# imx6_boot.net
KiCad netlist of a schematic drawn in Altium Designer
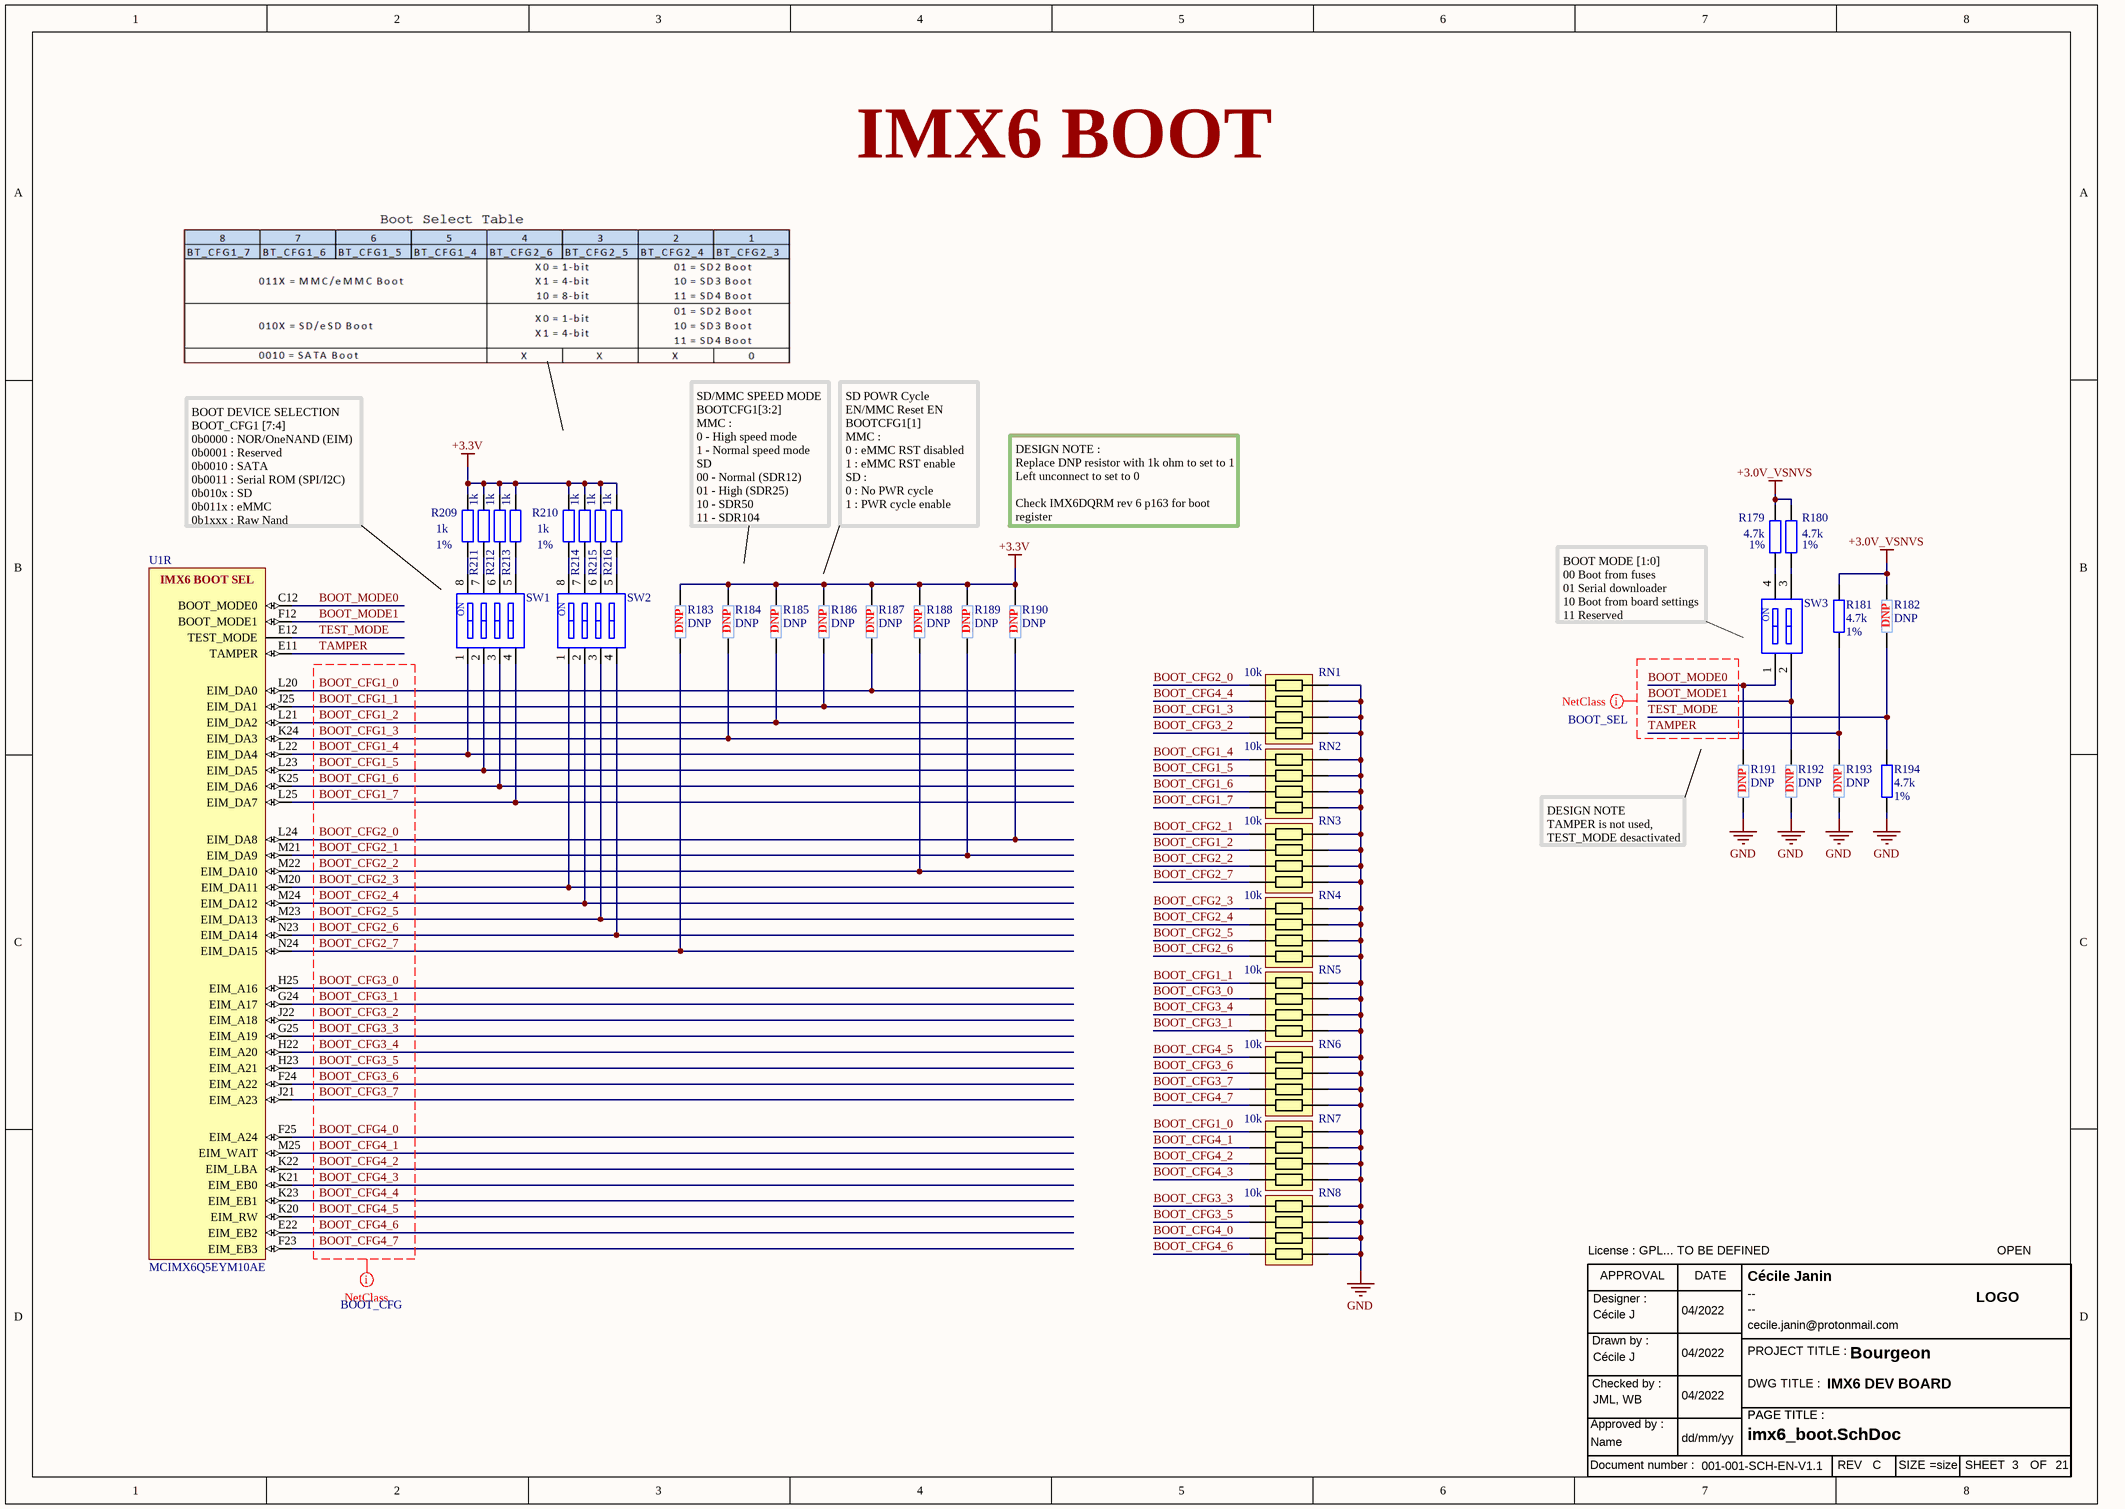
[diagram p0: imx6_boot.SchDoc]

(export (version "E")
  (design (tool "Eeschema 10.0.6"))
  (components
    (comp (ref "R179")
      (value "4.7k")
      (footprint "Res 0402/1005")
      (description "res 4.7k 1% 0402")
      (fields (field (name "POURCENTAGE") "1%"))
      (libsource (lib "First Board IMX6") (part "res 4.7k 1%"))
    )
    (comp (ref "R180")
      (value "4.7k")
      (footprint "Res 0402/1005")
      (description "res 4.7k 1% 0402")
      (fields (field (name "POURCENTAGE") "1%"))
      (libsource (lib "First Board IMX6") (part "res 4.7k 1%"))
    )
    (comp (ref "R181")
      (value "4.7k")
      (footprint "Res 0402/1005")
      (description "res 4.7k 1% 0402")
      (fields (field (name "POURCENTAGE") "1%"))
      (libsource (lib "First Board IMX6") (part "res 4.7k 1%"))
    )
    (comp (ref "R182")
      (value "DNP")
      (footprint "Res 0402/1005")
      (description "res DNP 0403")
      (libsource (lib "First Board IMX6") (part "res DNP 0402"))
    )
    (comp (ref "R183")
      (value "DNP")
      (footprint "Res 0402/1005")
      (description "res DNP 0403")
      (libsource (lib "First Board IMX6") (part "res DNP 0402"))
    )
    (comp (ref "R184")
      (value "DNP")
      (footprint "Res 0402/1005")
      (description "res DNP 0403")
      (libsource (lib "First Board IMX6") (part "res DNP 0402"))
    )
    (comp (ref "R185")
      (value "DNP")
      (footprint "Res 0402/1005")
      (description "res DNP 0403")
      (libsource (lib "First Board IMX6") (part "res DNP 0402"))
    )
    (comp (ref "R186")
      (value "DNP")
      (footprint "Res 0402/1005")
      (description "res DNP 0403")
      (libsource (lib "First Board IMX6") (part "res DNP 0402"))
    )
    (comp (ref "R187")
      (value "DNP")
      (footprint "Res 0402/1005")
      (description "res DNP 0403")
      (libsource (lib "First Board IMX6") (part "res DNP 0402"))
    )
    (comp (ref "R188")
      (value "DNP")
      (footprint "Res 0402/1005")
      (description "res DNP 0403")
      (libsource (lib "First Board IMX6") (part "res DNP 0402"))
    )
    (comp (ref "R189")
      (value "DNP")
      (footprint "Res 0402/1005")
      (description "res DNP 0403")
      (libsource (lib "First Board IMX6") (part "res DNP 0402"))
    )
    (comp (ref "R190")
      (value "DNP")
      (footprint "Res 0402/1005")
      (description "res DNP 0403")
      (libsource (lib "First Board IMX6") (part "res DNP 0402"))
    )
    (comp (ref "R191")
      (value "DNP")
      (footprint "Res 0402/1005")
      (description "res DNP 0403")
      (libsource (lib "First Board IMX6") (part "res DNP 0402"))
    )
    (comp (ref "R192")
      (value "DNP")
      (footprint "Res 0402/1005")
      (description "res DNP 0403")
      (libsource (lib "First Board IMX6") (part "res DNP 0402"))
    )
    (comp (ref "R193")
      (value "DNP")
      (footprint "Res 0402/1005")
      (description "res DNP 0403")
      (libsource (lib "First Board IMX6") (part "res DNP 0402"))
    )
    (comp (ref "R194")
      (value "4.7k")
      (footprint "Res 0402/1005")
      (description "res 4.7k 1% 0402")
      (fields (field (name "POURCENTAGE") "1%"))
      (libsource (lib "First Board IMX6") (part "res 4.7k 1%"))
    )
    (comp (ref "R209")
      (value "1k")
      (footprint "Res 0402/1005")
      (description "res 1k 1% 0402")
      (fields (field (name "POURCENTAGE") "1%"))
      (libsource (lib "First Board IMX6") (part "res 1k 1%"))
    )
    (comp (ref "R210")
      (value "1k")
      (footprint "Res 0402/1005")
      (description "res 1k 1% 0402")
      (fields (field (name "POURCENTAGE") "1%"))
      (libsource (lib "First Board IMX6") (part "res 1k 1%"))
    )
    (comp (ref "R211")
      (value "1k")
      (footprint "Res 0402/1005")
      (description "res 1k 1% 0402")
      (libsource (lib "First Board IMX6") (part "res 1k 1%"))
    )
    (comp (ref "R212")
      (value "1k")
      (footprint "Res 0402/1005")
      (description "res 1k 1% 0402")
      (libsource (lib "First Board IMX6") (part "res 1k 1%"))
    )
    (comp (ref "R213")
      (value "1k")
      (footprint "Res 0402/1005")
      (description "res 1k 1% 0402")
      (libsource (lib "First Board IMX6") (part "res 1k 1%"))
    )
    (comp (ref "R214")
      (value "1k")
      (footprint "Res 0402/1005")
      (description "res 1k 1% 0402")
      (libsource (lib "First Board IMX6") (part "res 1k 1%"))
    )
    (comp (ref "R215")
      (value "1k")
      (footprint "Res 0402/1005")
      (description "res 1k 1% 0402")
      (libsource (lib "First Board IMX6") (part "res 1k 1%"))
    )
    (comp (ref "R216")
      (value "1k")
      (footprint "Res 0402/1005")
      (description "res 1k 1% 0402")
      (libsource (lib "First Board IMX6") (part "res 1k 1%"))
    )
    (comp (ref "RN1")
      (value "10k")
      (footprint "res net x4  EXB-28V103JX")
      (description "resistor network 10k 5% x4 EXB-28V103JX")
      (libsource (lib "First Board IMX6") (part "res 10k net x4"))
    )
    (comp (ref "RN2")
      (value "10k")
      (footprint "res net x4  EXB-28V103JX")
      (description "resistor network 10k 5% x4 EXB-28V103JX")
      (libsource (lib "") (part "res 10k net x4_1"))
    )
    (comp (ref "RN3")
      (value "10k")
      (footprint "res net x4  EXB-28V103JX")
      (description "resistor network 10k 5% x4 EXB-28V103JX")
      (libsource (lib "First Board IMX6") (part "res 10k net x4"))
    )
    (comp (ref "RN4")
      (value "10k")
      (footprint "res net x4  EXB-28V103JX")
      (description "resistor network 10k 5% x4 EXB-28V103JX")
      (libsource (lib "") (part "res 10k net x4_1"))
    )
    (comp (ref "RN5")
      (value "10k")
      (footprint "res net x4  EXB-28V103JX")
      (description "resistor network 10k 5% x4 EXB-28V103JX")
      (libsource (lib "First Board IMX6") (part "res 10k net x4"))
    )
    (comp (ref "RN6")
      (value "10k")
      (footprint "res net x4  EXB-28V103JX")
      (description "resistor network 10k 5% x4 EXB-28V103JX")
      (libsource (lib "First Board IMX6") (part "res 10k net x4"))
    )
    (comp (ref "RN7")
      (value "10k")
      (footprint "res net x4  EXB-28V103JX")
      (description "resistor network 10k 5% x4 EXB-28V103JX")
      (libsource (lib "First Board IMX6") (part "res 10k net x4"))
    )
    (comp (ref "RN8")
      (value "10k")
      (footprint "res net x4  EXB-28V103JX")
      (description "resistor network 10k 5% x4 EXB-28V103JX")
      (libsource (lib "First Board IMX6") (part "res 10k net x4"))
    )
    (comp (ref "SW1")
      (value "416131160804")
      (footprint "DIP SWITCH x4 1.27mm")
      (libsource (lib "First Board IMX6") (part "DIP switch x4"))
    )
    (comp (ref "SW2")
      (value "416131160804")
      (footprint "DIP SWITCH x4 1.27mm")
      (libsource (lib "First Board IMX6") (part "DIP switch x4"))
    )
    (comp (ref "SW3")
      (value "416131160802")
      (footprint "DIP switch x2 1.27mm")
      (libsource (lib "First Board IMX6") (part "DIP switch x2"))
    )
    (comp (ref "TB20")
      (value "Title bloc ANSI modified")
      (libsource (lib "First Board IMX6") (part "Title bloc ANSI"))
    )
    (comp (ref "U1")
      (value "MCIMX6Q5EYM10AE")
      (footprint "FRES-2197-01")
      (fields
        (field (name "PARTNUMBER") "MCIMX6Q5EYM10ACR")
        (field (name "MANUFACTURER") "Freescale Semiconductor")
      )
      (libsource (lib "First Board IMX6") (part "IMX6Q5EYM10AE"))
    )
  )
  (nets
    (net (code "1") (name "+3.0V_VSNVS") (class "Default")
      (node (ref "R179") (pin "2") (pintype "passive"))
      (node (ref "R180") (pin "2") (pintype "passive"))
      (node (ref "R181") (pin "2") (pintype "passive"))
      (node (ref "R182") (pin "2") (pintype "passive"))
    )
    (net (code "2") (name "+3.3V") (class "Default")
      (node (ref "R183") (pin "2") (pintype "passive"))
      (node (ref "R184") (pin "2") (pintype "passive"))
      (node (ref "R185") (pin "2") (pintype "passive"))
      (node (ref "R186") (pin "2") (pintype "passive"))
      (node (ref "R187") (pin "2") (pintype "passive"))
      (node (ref "R188") (pin "2") (pintype "passive"))
      (node (ref "R189") (pin "2") (pintype "passive"))
      (node (ref "R190") (pin "2") (pintype "passive"))
      (node (ref "R209") (pin "2") (pintype "passive"))
      (node (ref "R210") (pin "2") (pintype "passive"))
      (node (ref "R211") (pin "2") (pintype "passive"))
      (node (ref "R212") (pin "2") (pintype "passive"))
      (node (ref "R213") (pin "2") (pintype "passive"))
      (node (ref "R214") (pin "2") (pintype "passive"))
      (node (ref "R215") (pin "2") (pintype "passive"))
      (node (ref "R216") (pin "2") (pintype "passive"))
    )
    (net (code "3") (name "/BOOT_CFG1_0") (class "Default")
      (node (ref "R187") (pin "1") (pintype "passive"))
      (node (ref "RN7") (pin "1") (pinfunction "1_1") (pintype "passive"))
      (node (ref "U1") (pin "L20") (pinfunction "EIM_DA0_L20") (pintype "bidirectional"))
    )
    (net (code "4") (name "/BOOT_CFG1_1") (class "Default")
      (node (ref "R186") (pin "1") (pintype "passive"))
      (node (ref "RN5") (pin "1") (pinfunction "1_1") (pintype "passive"))
      (node (ref "U1") (pin "J25") (pinfunction "EIM_DA1_J25") (pintype "bidirectional"))
    )
    (net (code "5") (name "/BOOT_CFG1_2") (class "Default")
      (node (ref "R185") (pin "1") (pintype "passive"))
      (node (ref "RN3") (pin "2") (pinfunction "2_2") (pintype "passive"))
      (node (ref "U1") (pin "L21") (pinfunction "EIM_DA2_L21") (pintype "bidirectional"))
    )
    (net (code "6") (name "/BOOT_CFG1_3") (class "Default")
      (node (ref "R184") (pin "1") (pintype "passive"))
      (node (ref "RN1") (pin "3") (pinfunction "3_3") (pintype "passive"))
      (node (ref "U1") (pin "K24") (pinfunction "EIM_DA3_K24") (pintype "bidirectional"))
    )
    (net (code "7") (name "/BOOT_CFG1_4") (class "Default")
      (node (ref "RN2") (pin "8") (pinfunction "8_8") (pintype "passive"))
      (node (ref "SW1") (pin "1") (pinfunction "1_1") (pintype "passive"))
      (node (ref "U1") (pin "L22") (pinfunction "EIM_DA4_L22") (pintype "bidirectional"))
    )
    (net (code "8") (name "/BOOT_CFG1_5") (class "Default")
      (node (ref "RN2") (pin "7") (pinfunction "7_7") (pintype "passive"))
      (node (ref "SW1") (pin "2") (pinfunction "2_2") (pintype "passive"))
      (node (ref "U1") (pin "L23") (pinfunction "EIM_DA5_L23") (pintype "bidirectional"))
    )
    (net (code "9") (name "/BOOT_CFG1_6") (class "Default")
      (node (ref "RN2") (pin "6") (pinfunction "1_6") (pintype "passive"))
      (node (ref "SW1") (pin "3") (pinfunction "3_3") (pintype "passive"))
      (node (ref "U1") (pin "K25") (pinfunction "EIM_DA6_K25") (pintype "bidirectional"))
    )
    (net (code "10") (name "/BOOT_CFG1_7") (class "Default")
      (node (ref "RN2") (pin "5") (pinfunction "5_5") (pintype "passive"))
      (node (ref "SW1") (pin "4") (pinfunction "4_4") (pintype "passive"))
      (node (ref "U1") (pin "L25") (pinfunction "EIM_DA7_L25") (pintype "bidirectional"))
    )
    (net (code "11") (name "/BOOT_CFG2_0") (class "Default")
      (node (ref "R190") (pin "1") (pintype "passive"))
      (node (ref "RN1") (pin "1") (pinfunction "1_1") (pintype "passive"))
      (node (ref "U1") (pin "L24") (pinfunction "EIM_DA8_L24") (pintype "bidirectional"))
    )
    (net (code "12") (name "/BOOT_CFG2_1") (class "Default")
      (node (ref "R189") (pin "1") (pintype "passive"))
      (node (ref "RN3") (pin "1") (pinfunction "1_1") (pintype "passive"))
      (node (ref "U1") (pin "M21") (pinfunction "EIM_DA9_M21") (pintype "bidirectional"))
    )
    (net (code "13") (name "/BOOT_CFG2_2") (class "Default")
      (node (ref "R188") (pin "1") (pintype "passive"))
      (node (ref "RN3") (pin "3") (pinfunction "3_3") (pintype "passive"))
      (node (ref "U1") (pin "M22") (pinfunction "EIM_DA10_M22") (pintype "bidirectional"))
    )
    (net (code "14") (name "/BOOT_CFG2_3") (class "Default")
      (node (ref "RN4") (pin "8") (pinfunction "8_8") (pintype "passive"))
      (node (ref "SW2") (pin "1") (pinfunction "1_1") (pintype "passive"))
      (node (ref "U1") (pin "M20") (pinfunction "EIM_DA11_M20") (pintype "bidirectional"))
    )
    (net (code "15") (name "/BOOT_CFG2_4") (class "Default")
      (node (ref "RN4") (pin "7") (pinfunction "7_7") (pintype "passive"))
      (node (ref "SW2") (pin "2") (pinfunction "2_2") (pintype "passive"))
      (node (ref "U1") (pin "M24") (pinfunction "EIM_DA12_M24") (pintype "bidirectional"))
    )
    (net (code "16") (name "/BOOT_CFG2_5") (class "Default")
      (node (ref "RN4") (pin "6") (pinfunction "1_6") (pintype "passive"))
      (node (ref "SW2") (pin "3") (pinfunction "3_3") (pintype "passive"))
      (node (ref "U1") (pin "M23") (pinfunction "EIM_DA13_M23") (pintype "bidirectional"))
    )
    (net (code "17") (name "/BOOT_CFG2_6") (class "Default")
      (node (ref "RN4") (pin "5") (pinfunction "5_5") (pintype "passive"))
      (node (ref "SW2") (pin "4") (pinfunction "4_4") (pintype "passive"))
      (node (ref "U1") (pin "N23") (pinfunction "EIM_DA14_N23") (pintype "bidirectional"))
    )
    (net (code "18") (name "/BOOT_CFG2_7") (class "Default")
      (node (ref "R183") (pin "1") (pintype "passive"))
      (node (ref "RN3") (pin "4") (pinfunction "4_4") (pintype "passive"))
      (node (ref "U1") (pin "N24") (pinfunction "EIM_DA15_N24") (pintype "bidirectional"))
    )
    (net (code "19") (name "/BOOT_CFG3_0") (class "Default")
      (node (ref "RN5") (pin "2") (pinfunction "2_2") (pintype "passive"))
      (node (ref "U1") (pin "H25") (pinfunction "EIM_A16_H25") (pintype "bidirectional"))
    )
    (net (code "20") (name "/BOOT_CFG3_1") (class "Default")
      (node (ref "RN5") (pin "4") (pinfunction "4_4") (pintype "passive"))
      (node (ref "U1") (pin "G24") (pinfunction "EIM_A17_G24") (pintype "bidirectional"))
    )
    (net (code "21") (name "/BOOT_CFG3_2") (class "Default")
      (node (ref "RN1") (pin "4") (pinfunction "4_4") (pintype "passive"))
      (node (ref "U1") (pin "J22") (pinfunction "EIM_A18_J22") (pintype "bidirectional"))
    )
    (net (code "22") (name "/BOOT_CFG3_3") (class "Default")
      (node (ref "RN8") (pin "1") (pinfunction "1_1") (pintype "passive"))
      (node (ref "U1") (pin "G25") (pinfunction "EIM_A19_G25") (pintype "bidirectional"))
    )
    (net (code "23") (name "/BOOT_CFG3_4") (class "Default")
      (node (ref "RN5") (pin "3") (pinfunction "3_3") (pintype "passive"))
      (node (ref "U1") (pin "H22") (pinfunction "EIM_A20_H22") (pintype "bidirectional"))
    )
    (net (code "24") (name "/BOOT_CFG3_5") (class "Default")
      (node (ref "RN8") (pin "2") (pinfunction "2_2") (pintype "passive"))
      (node (ref "U1") (pin "H23") (pinfunction "EIM_A21_H23") (pintype "bidirectional"))
    )
    (net (code "25") (name "/BOOT_CFG3_6") (class "Default")
      (node (ref "RN6") (pin "2") (pinfunction "2_2") (pintype "passive"))
      (node (ref "U1") (pin "F24") (pinfunction "EIM_A22_F24") (pintype "bidirectional"))
    )
    (net (code "26") (name "/BOOT_CFG3_7") (class "Default")
      (node (ref "RN6") (pin "3") (pinfunction "3_3") (pintype "passive"))
      (node (ref "U1") (pin "J21") (pinfunction "EIM_A23_J21") (pintype "bidirectional"))
    )
    (net (code "27") (name "/BOOT_CFG4_0") (class "Default")
      (node (ref "RN8") (pin "3") (pinfunction "3_3") (pintype "passive"))
      (node (ref "U1") (pin "F25") (pinfunction "EIM_A24_F25") (pintype "bidirectional"))
    )
    (net (code "28") (name "/BOOT_CFG4_1") (class "Default")
      (node (ref "RN7") (pin "2") (pinfunction "2_2") (pintype "passive"))
      (node (ref "U1") (pin "M25") (pinfunction "EIM_WAIT_M25") (pintype "bidirectional"))
    )
    (net (code "29") (name "/BOOT_CFG4_2") (class "Default")
      (node (ref "RN7") (pin "3") (pinfunction "3_3") (pintype "passive"))
      (node (ref "U1") (pin "K22") (pinfunction "EIM_LBA_K22") (pintype "bidirectional"))
    )
    (net (code "30") (name "/BOOT_CFG4_3") (class "Default")
      (node (ref "RN7") (pin "4") (pinfunction "4_4") (pintype "passive"))
      (node (ref "U1") (pin "K21") (pinfunction "EIM_EB0_K21") (pintype "bidirectional"))
    )
    (net (code "31") (name "/BOOT_CFG4_4") (class "Default")
      (node (ref "RN1") (pin "2") (pinfunction "2_2") (pintype "passive"))
      (node (ref "U1") (pin "K23") (pinfunction "EIM_EB1_K23") (pintype "bidirectional"))
    )
    (net (code "32") (name "/BOOT_CFG4_5") (class "Default")
      (node (ref "RN6") (pin "1") (pinfunction "1_1") (pintype "passive"))
      (node (ref "U1") (pin "K20") (pinfunction "EIM_RW_K20") (pintype "bidirectional"))
    )
    (net (code "33") (name "/BOOT_CFG4_6") (class "Default")
      (node (ref "RN8") (pin "4") (pinfunction "4_4") (pintype "passive"))
      (node (ref "U1") (pin "E22") (pinfunction "EIM_EB2_E22") (pintype "bidirectional"))
    )
    (net (code "34") (name "/BOOT_CFG4_7") (class "Default")
      (node (ref "RN6") (pin "4") (pinfunction "4_4") (pintype "passive"))
      (node (ref "U1") (pin "F23") (pinfunction "EIM_EB3_F23") (pintype "bidirectional"))
    )
    (net (code "35") (name "/BOOT_MODE0") (class "Default")
      (node (ref "R191") (pin "2") (pintype "passive"))
      (node (ref "SW3") (pin "1") (pinfunction "1_1") (pintype "passive"))
      (node (ref "U1") (pin "C12") (pinfunction "BOOT_MODE0_C12") (pintype "bidirectional"))
    )
    (net (code "36") (name "/BOOT_MODE1") (class "Default")
      (node (ref "R192") (pin "2") (pintype "passive"))
      (node (ref "SW3") (pin "2") (pinfunction "2_2") (pintype "passive"))
      (node (ref "U1") (pin "F12") (pinfunction "BOOT_MODE1_F12") (pintype "bidirectional"))
    )
    (net (code "37") (name "/TAMPER") (class "Default")
      (node (ref "R181") (pin "1") (pintype "passive"))
      (node (ref "R193") (pin "2") (pintype "passive"))
      (node (ref "U1") (pin "E11") (pinfunction "TAMPER_E11") (pintype "bidirectional"))
    )
    (net (code "38") (name "/TEST_MODE") (class "Default")
      (node (ref "R182") (pin "1") (pintype "passive"))
      (node (ref "R194") (pin "2") (pintype "passive"))
      (node (ref "U1") (pin "E12") (pinfunction "TEST_MODE_E12") (pintype "passive"))
    )
    (net (code "39") (name "GND") (class "Default")
      (node (ref "R191") (pin "1") (pintype "passive"))
      (node (ref "R192") (pin "1") (pintype "passive"))
      (node (ref "R193") (pin "1") (pintype "passive"))
      (node (ref "R194") (pin "1") (pintype "passive"))
      (node (ref "RN1") (pin "5") (pinfunction "5_5") (pintype "passive"))
      (node (ref "RN1") (pin "6") (pinfunction "1_6") (pintype "passive"))
      (node (ref "RN1") (pin "7") (pinfunction "7_7") (pintype "passive"))
      (node (ref "RN1") (pin "8") (pinfunction "8_8") (pintype "passive"))
      (node (ref "RN2") (pin "1") (pinfunction "1_1") (pintype "passive"))
      (node (ref "RN2") (pin "2") (pinfunction "2_2") (pintype "passive"))
      (node (ref "RN2") (pin "3") (pinfunction "3_3") (pintype "passive"))
      (node (ref "RN2") (pin "4") (pinfunction "4_4") (pintype "passive"))
      (node (ref "RN3") (pin "5") (pinfunction "5_5") (pintype "passive"))
      (node (ref "RN3") (pin "6") (pinfunction "1_6") (pintype "passive"))
      (node (ref "RN3") (pin "7") (pinfunction "7_7") (pintype "passive"))
      (node (ref "RN3") (pin "8") (pinfunction "8_8") (pintype "passive"))
      (node (ref "RN4") (pin "1") (pinfunction "1_1") (pintype "passive"))
      (node (ref "RN4") (pin "2") (pinfunction "2_2") (pintype "passive"))
      (node (ref "RN4") (pin "3") (pinfunction "3_3") (pintype "passive"))
      (node (ref "RN4") (pin "4") (pinfunction "4_4") (pintype "passive"))
      (node (ref "RN5") (pin "5") (pinfunction "5_5") (pintype "passive"))
      (node (ref "RN5") (pin "6") (pinfunction "1_6") (pintype "passive"))
      (node (ref "RN5") (pin "7") (pinfunction "7_7") (pintype "passive"))
      (node (ref "RN5") (pin "8") (pinfunction "8_8") (pintype "passive"))
      (node (ref "RN6") (pin "5") (pinfunction "5_5") (pintype "passive"))
      (node (ref "RN6") (pin "6") (pinfunction "1_6") (pintype "passive"))
      (node (ref "RN6") (pin "7") (pinfunction "7_7") (pintype "passive"))
      (node (ref "RN6") (pin "8") (pinfunction "8_8") (pintype "passive"))
      (node (ref "RN7") (pin "5") (pinfunction "5_5") (pintype "passive"))
      (node (ref "RN7") (pin "6") (pinfunction "1_6") (pintype "passive"))
      (node (ref "RN7") (pin "7") (pinfunction "7_7") (pintype "passive"))
      (node (ref "RN7") (pin "8") (pinfunction "8_8") (pintype "passive"))
      (node (ref "RN8") (pin "5") (pinfunction "5_5") (pintype "passive"))
      (node (ref "RN8") (pin "6") (pinfunction "1_6") (pintype "passive"))
      (node (ref "RN8") (pin "7") (pinfunction "7_7") (pintype "passive"))
      (node (ref "RN8") (pin "8") (pinfunction "8_8") (pintype "passive"))
    )
    (net (code "40") (name "Net-(R179-Pad1)") (class "Default")
      (node (ref "R179") (pin "1") (pintype "passive"))
      (node (ref "SW3") (pin "4") (pinfunction "4_4") (pintype "passive"))
    )
    (net (code "41") (name "Net-(R180-Pad1)") (class "Default")
      (node (ref "R180") (pin "1") (pintype "passive"))
      (node (ref "SW3") (pin "3") (pinfunction "3_3") (pintype "passive"))
    )
    (net (code "42") (name "Net-(R209-Pad1)") (class "Default")
      (node (ref "R209") (pin "1") (pintype "passive"))
      (node (ref "SW1") (pin "8") (pinfunction "8_8") (pintype "passive"))
    )
    (net (code "43") (name "Net-(R210-Pad1)") (class "Default")
      (node (ref "R210") (pin "1") (pintype "passive"))
      (node (ref "SW2") (pin "8") (pinfunction "8_8") (pintype "passive"))
    )
    (net (code "44") (name "Net-(R211-Pad1)") (class "Default")
      (node (ref "R211") (pin "1") (pintype "passive"))
      (node (ref "SW1") (pin "7") (pinfunction "7_7") (pintype "passive"))
    )
    (net (code "45") (name "Net-(R212-Pad1)") (class "Default")
      (node (ref "R212") (pin "1") (pintype "passive"))
      (node (ref "SW1") (pin "6") (pinfunction "6_6") (pintype "passive"))
    )
    (net (code "46") (name "Net-(R213-Pad1)") (class "Default")
      (node (ref "R213") (pin "1") (pintype "passive"))
      (node (ref "SW1") (pin "5") (pinfunction "5_5") (pintype "passive"))
    )
    (net (code "47") (name "Net-(R214-Pad1)") (class "Default")
      (node (ref "R214") (pin "1") (pintype "passive"))
      (node (ref "SW2") (pin "7") (pinfunction "7_7") (pintype "passive"))
    )
    (net (code "48") (name "Net-(R215-Pad1)") (class "Default")
      (node (ref "R215") (pin "1") (pintype "passive"))
      (node (ref "SW2") (pin "6") (pinfunction "6_6") (pintype "passive"))
    )
    (net (code "49") (name "Net-(R216-Pad1)") (class "Default")
      (node (ref "R216") (pin "1") (pintype "passive"))
      (node (ref "SW2") (pin "5") (pinfunction "5_5") (pintype "passive"))
    )
  )
)
